# esp-01_lite2_us.net
KiCad netlist of a schematic drawn in EAGLE
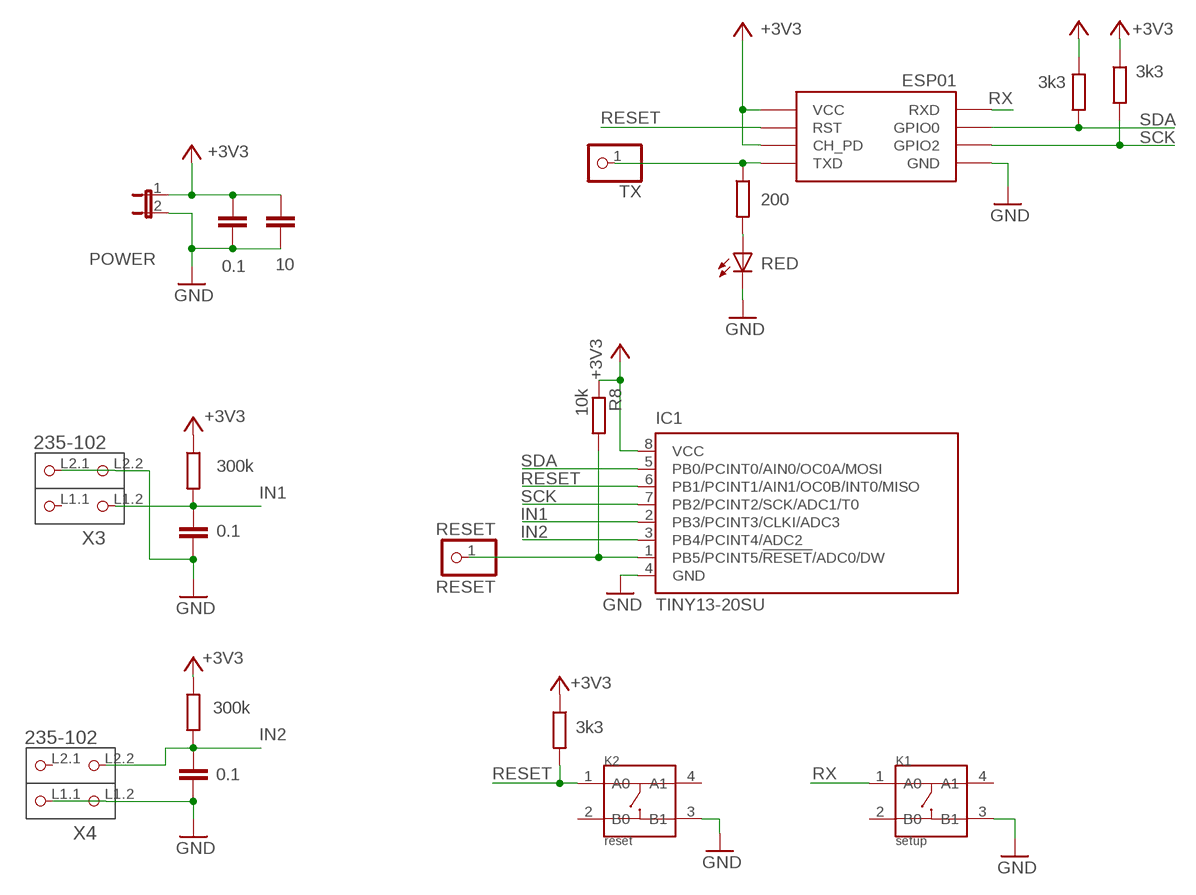
[diagram p0: schematic, sheet 1]

(export (version "E")
  (design (tool "Eeschema 10.0.6"))
  (components
    (comp (ref "C1")
      (value "0.1")
      (footprint "eagle-import:C0805")
      (fields (field (name "MKF") "0.1"))
      (libsource (lib "eagle-import") (part "C-EUC0805"))
    )
    (comp (ref "C2")
      (value "0.1")
      (footprint "eagle-import:C0805")
      (libsource (lib "eagle-import") (part "C-EUC0805"))
    )
    (comp (ref "C3")
      (value "0.1")
      (footprint "eagle-import:C0805")
      (fields (field (name "MKF") "0.1"))
      (libsource (lib "eagle-import") (part "C-EUC0805"))
    )
    (comp (ref "C4")
      (value "10")
      (footprint "eagle-import:C025-024X044")
      (fields (field (name "MKF") "0.1"))
      (libsource (lib "eagle-import") (part "resistor_C-EU025-024X044"))
    )
    (comp (ref "IC1")
      (value "TINY13-20SU")
      (footprint "eagle-import:8S2")
      (fields (field (name "MPN") "ATTINY13-20SU"))
      (libsource (lib "eagle-import") (part "TINY13SU-20"))
    )
    (comp (ref "JP2")
      (value "POWER")
      (footprint "eagle-import:JP1")
      (libsource (lib "eagle-import") (part "JP1E"))
    )
    (comp (ref "K1")
      (value "setup")
      (footprint "eagle-import:SW4-6.0X6.0X5.0MM")
      (fields (field (name "MPN") "TS-1109"))
      (libsource (lib "eagle-import") (part "DIP-BUTTON-4P"))
    )
    (comp (ref "K2")
      (value "reset")
      (footprint "eagle-import:SW4-6.0X6.0X5.0MM")
      (fields (field (name "MPN") "TS-1109"))
      (libsource (lib "eagle-import") (part "DIP-BUTTON-4P"))
    )
    (comp (ref "LED1")
      (value "RED")
      (footprint "eagle-import:SML0805")
      (libsource (lib "eagle-import") (part "LEDSML0805"))
    )
    (comp (ref "R2")
      (value "3k3")
      (footprint "eagle-import:R0805")
      (fields (field (name "OM") "3k6"))
      (libsource (lib "eagle-import") (part "R-EU_R0805"))
    )
    (comp (ref "R3")
      (value "3k3")
      (footprint "eagle-import:0207_5V")
      (fields (field (name "OM") "3k6"))
      (libsource (lib "eagle-import") (part "resistor_R-EU_0207/5V"))
    )
    (comp (ref "R4")
      (value "200")
      (footprint "eagle-import:0207_5V")
      (fields (field (name "OM") "200"))
      (libsource (lib "eagle-import") (part "resistor_348_R-EU_0207/5V"))
    )
    (comp (ref "R5")
      (value "3k3")
      (footprint "eagle-import:R0805")
      (fields (field (name "OM") "3k6"))
      (libsource (lib "eagle-import") (part "R-EU_R0805"))
    )
    (comp (ref "R8")
      (value "10k")
      (footprint "eagle-import:R0805")
      (fields (field (name "OM") "3k6"))
      (libsource (lib "eagle-import") (part "R-EU_R0805"))
    )
    (comp (ref "R10")
      (value "300k")
      (footprint "eagle-import:R0805")
      (fields (field (name "OM") "3k6"))
      (libsource (lib "eagle-import") (part "R-EU_R0805"))
    )
    (comp (ref "R11")
      (value "300k")
      (footprint "eagle-import:0207_7")
      (fields (field (name "OM") "3k6"))
      (libsource (lib "eagle-import") (part "resistor_348_R-EU_0207/7"))
    )
    (comp (ref "RESET")
      (value "RESET")
      (footprint "eagle-import:1X01")
      (libsource (lib "eagle-import") (part "PINHD-1X1"))
    )
    (comp (ref "TX")
      (value "TX")
      (footprint "eagle-import:1X01")
      (libsource (lib "eagle-import") (part "PINHD-1X1"))
    )
    (comp (ref "U$1")
      (value "ESP01")
      (footprint "eagle-import:ESP01")
      (libsource (lib "eagle-import") (part "ESP01"))
    )
    (comp (ref "X3")
      (value "235-102")
      (footprint "eagle-import:P-235-102")
      (libsource (lib "eagle-import") (part "235-102"))
    )
    (comp (ref "X4")
      (value "235-102")
      (footprint "eagle-import:P-235-102")
      (libsource (lib "eagle-import") (part "235-102"))
    )
  )
  (nets
    (net (code "1") (name "+3V3") (class "Default")
      (node (ref "C3") (pin "1") (pinfunction "1_1") (pintype "passive"))
      (node (ref "C4") (pin "1") (pinfunction "1_1") (pintype "passive"))
      (node (ref "IC1") (pin "8") (pinfunction "VCC_8") (pintype "power_in"))
      (node (ref "JP2") (pin "1") (pinfunction "1_1") (pintype "passive"))
      (node (ref "R10") (pin "1") (pinfunction "1_1") (pintype "passive"))
      (node (ref "R11") (pin "1") (pinfunction "1_1") (pintype "passive"))
      (node (ref "R2") (pin "1") (pinfunction "1_1") (pintype "passive"))
      (node (ref "R3") (pin "1") (pinfunction "1_1") (pintype "passive"))
      (node (ref "R5") (pin "1") (pinfunction "1_1") (pintype "passive"))
      (node (ref "R8") (pin "1") (pinfunction "1_1") (pintype "passive"))
      (node (ref "U$1") (pin "CH_PD") (pinfunction "CH_PD_CH_PD") (pintype "bidirectional"))
      (node (ref "U$1") (pin "VCC") (pinfunction "VCC_VCC") (pintype "bidirectional"))
    )
    (net (code "2") (name "/IN1") (class "Default")
      (node (ref "C1") (pin "1") (pinfunction "1_1") (pintype "passive"))
      (node (ref "IC1") (pin "2") (pinfunction "PB3/PCINT3/CLKI/ADC3_2") (pintype "bidirectional"))
      (node (ref "R10") (pin "2") (pinfunction "2_2") (pintype "passive"))
      (node (ref "X3") (pin "L1.2") (pinfunction "P1.2_L1.2") (pintype "bidirectional"))
    )
    (net (code "3") (name "/IN2") (class "Default")
      (node (ref "C2") (pin "2") (pinfunction "2_2") (pintype "passive"))
      (node (ref "IC1") (pin "3") (pinfunction "PB4/PCINT4/ADC2_3") (pintype "bidirectional"))
      (node (ref "R11") (pin "2") (pinfunction "2_2") (pintype "passive"))
      (node (ref "X4") (pin "L2.2") (pinfunction "P2.2_L2.2") (pintype "bidirectional"))
    )
    (net (code "4") (name "/RESET") (class "Default")
      (node (ref "IC1") (pin "6") (pinfunction "PB1/PCINT1/AIN1/OC0B/INT0/MISO_6") (pintype "bidirectional"))
      (node (ref "K2") (pin "1") (pinfunction "A0_1") (pintype "bidirectional"))
      (node (ref "R5") (pin "2") (pinfunction "2_2") (pintype "passive"))
      (node (ref "U$1") (pin "RST") (pinfunction "RST_RST") (pintype "bidirectional"))
    )
    (net (code "5") (name "/RX") (class "Default")
      (node (ref "K1") (pin "1") (pinfunction "A0_1") (pintype "bidirectional"))
      (node (ref "U$1") (pin "RX") (pinfunction "RXD_RX") (pintype "bidirectional"))
    )
    (net (code "6") (name "/SCK") (class "Default")
      (node (ref "IC1") (pin "7") (pinfunction "PB2/PCINT2/SCK/ADC1/T0_7") (pintype "bidirectional"))
      (node (ref "R2") (pin "2") (pinfunction "2_2") (pintype "passive"))
      (node (ref "U$1") (pin "GPIO2") (pinfunction "GPIO2_GPIO2") (pintype "bidirectional"))
    )
    (net (code "7") (name "/SDA") (class "Default")
      (node (ref "IC1") (pin "5") (pinfunction "PB0/PCINT0/AIN0/OC0A/MOSI_5") (pintype "bidirectional"))
      (node (ref "R3") (pin "2") (pinfunction "2_2") (pintype "passive"))
      (node (ref "U$1") (pin "GPIO0") (pinfunction "GPIO0_GPIO0") (pintype "bidirectional"))
    )
    (net (code "8") (name "GND") (class "Default")
      (node (ref "C1") (pin "2") (pinfunction "2_2") (pintype "passive"))
      (node (ref "C2") (pin "1") (pinfunction "1_1") (pintype "passive"))
      (node (ref "C3") (pin "2") (pinfunction "2_2") (pintype "passive"))
      (node (ref "C4") (pin "2") (pinfunction "2_2") (pintype "passive"))
      (node (ref "IC1") (pin "4") (pinfunction "GND_4") (pintype "power_in"))
      (node (ref "JP2") (pin "2") (pinfunction "2_2") (pintype "passive"))
      (node (ref "K1") (pin "3") (pinfunction "B1_3") (pintype "bidirectional"))
      (node (ref "K2") (pin "3") (pinfunction "B1_3") (pintype "bidirectional"))
      (node (ref "LED1") (pin "C") (pinfunction "C_C") (pintype "passive"))
      (node (ref "U$1") (pin "GND") (pinfunction "GND_GND") (pintype "bidirectional"))
      (node (ref "X3") (pin "L2.1") (pinfunction "P2.1_L2.1") (pintype "bidirectional"))
      (node (ref "X3") (pin "L2.2") (pinfunction "P2.2_L2.2") (pintype "bidirectional"))
      (node (ref "X4") (pin "L1.1") (pinfunction "P1.1_L1.1") (pintype "bidirectional"))
      (node (ref "X4") (pin "L1.2") (pinfunction "P1.2_L1.2") (pintype "bidirectional"))
    )
    (net (code "9") (name "Net-(IC1-PB5{slash}PCINT5{slash}~{RESET}{slash}ADC0{slash}DW)") (class "Default")
      (node (ref "IC1") (pin "1") (pinfunction "PB5/PCINT5/~{RESET}/ADC0/DW_1") (pintype "bidirectional"))
      (node (ref "R8") (pin "2") (pinfunction "2_2") (pintype "passive"))
      (node (ref "RESET") (pin "1") (pinfunction "1_1") (pintype "passive"))
    )
    (net (code "10") (name "Net-(LED1-PadA)") (class "Default")
      (node (ref "LED1") (pin "A") (pinfunction "A_A") (pintype "passive"))
      (node (ref "R4") (pin "2") (pinfunction "2_2") (pintype "passive"))
    )
    (net (code "11") (name "Net-(U$1-TXD)") (class "Default")
      (node (ref "R4") (pin "1") (pinfunction "1_1") (pintype "passive"))
      (node (ref "TX") (pin "1") (pinfunction "1_1") (pintype "passive"))
      (node (ref "U$1") (pin "TX") (pinfunction "TXD_TX") (pintype "bidirectional"))
    )
    (net (code "12") (name "unconnected-(K1-A1-Pad4)") (class "Default")
      (node (ref "K1") (pin "4") (pinfunction "A1_4") (pintype "bidirectional"))
    )
    (net (code "13") (name "unconnected-(K1-B0-Pad2)") (class "Default")
      (node (ref "K1") (pin "2") (pinfunction "B0_2") (pintype "bidirectional"))
    )
    (net (code "14") (name "unconnected-(K2-A1-Pad4)") (class "Default")
      (node (ref "K2") (pin "4") (pinfunction "A1_4") (pintype "bidirectional"))
    )
    (net (code "15") (name "unconnected-(K2-B0-Pad2)") (class "Default")
      (node (ref "K2") (pin "2") (pinfunction "B0_2") (pintype "bidirectional"))
    )
    (net (code "16") (name "unconnected-(X3-P1.1-PadL1.1)") (class "Default")
      (node (ref "X3") (pin "L1.1") (pinfunction "P1.1_L1.1") (pintype "bidirectional"))
    )
    (net (code "17") (name "unconnected-(X4-P2.1-PadL2.1)") (class "Default")
      (node (ref "X4") (pin "L2.1") (pinfunction "P2.1_L2.1") (pintype "bidirectional"))
    )
  )
)
